# LORA.net
KiCad netlist of a schematic drawn in Altium Designer
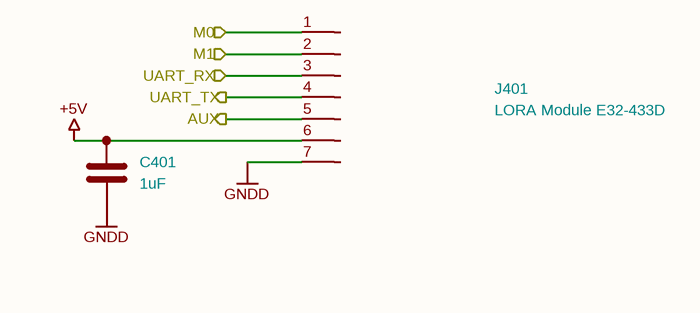
[diagram p0: LORA.SchDoc]

(export (version "E")
  (design (tool "Eeschema 10.0.6"))
  (components
    (comp (ref "C401")
      (value "1uF")
      (footprint "C_0603_1608Metric_Pad1.08x0.95mm_HandSolder")
      (libsource (lib "Device") (part "C"))
    )
    (comp (ref "J401")
      (value "LORA Module E32-433D")
      (footprint "E32-433T33D-EDITEDSIZE")
      (libsource (lib "Connector") (part "Conn_01x07_Socket"))
    )
  )
  (nets
    (net (code "1") (name "+5V") (class "Default")
      (node (ref "C401") (pin "1") (pinfunction "1_1") (pintype "passive"))
      (node (ref "J401") (pin "6") (pinfunction "Pin_6_6") (pintype "passive"))
    )
    (net (code "2") (name "/AUX") (class "Default")
      (node (ref "J401") (pin "5") (pinfunction "Pin_5_5") (pintype "passive"))
    )
    (net (code "3") (name "/M0") (class "Default")
      (node (ref "J401") (pin "1") (pinfunction "Pin_1_1") (pintype "passive"))
    )
    (net (code "4") (name "/M1") (class "Default")
      (node (ref "J401") (pin "2") (pinfunction "Pin_2_2") (pintype "passive"))
    )
    (net (code "5") (name "/UART_RX") (class "Default")
      (node (ref "J401") (pin "3") (pinfunction "Pin_3_3") (pintype "passive"))
    )
    (net (code "6") (name "/UART_TX") (class "Default")
      (node (ref "J401") (pin "4") (pinfunction "Pin_4_4") (pintype "passive"))
    )
    (net (code "7") (name "GNDD") (class "Default")
      (node (ref "C401") (pin "2") (pinfunction "2_2") (pintype "passive"))
      (node (ref "J401") (pin "7") (pinfunction "Pin_7_7") (pintype "passive"))
    )
  )
)
